# GoPiGoMod.net
KiCad netlist of a schematic drawn in EAGLE
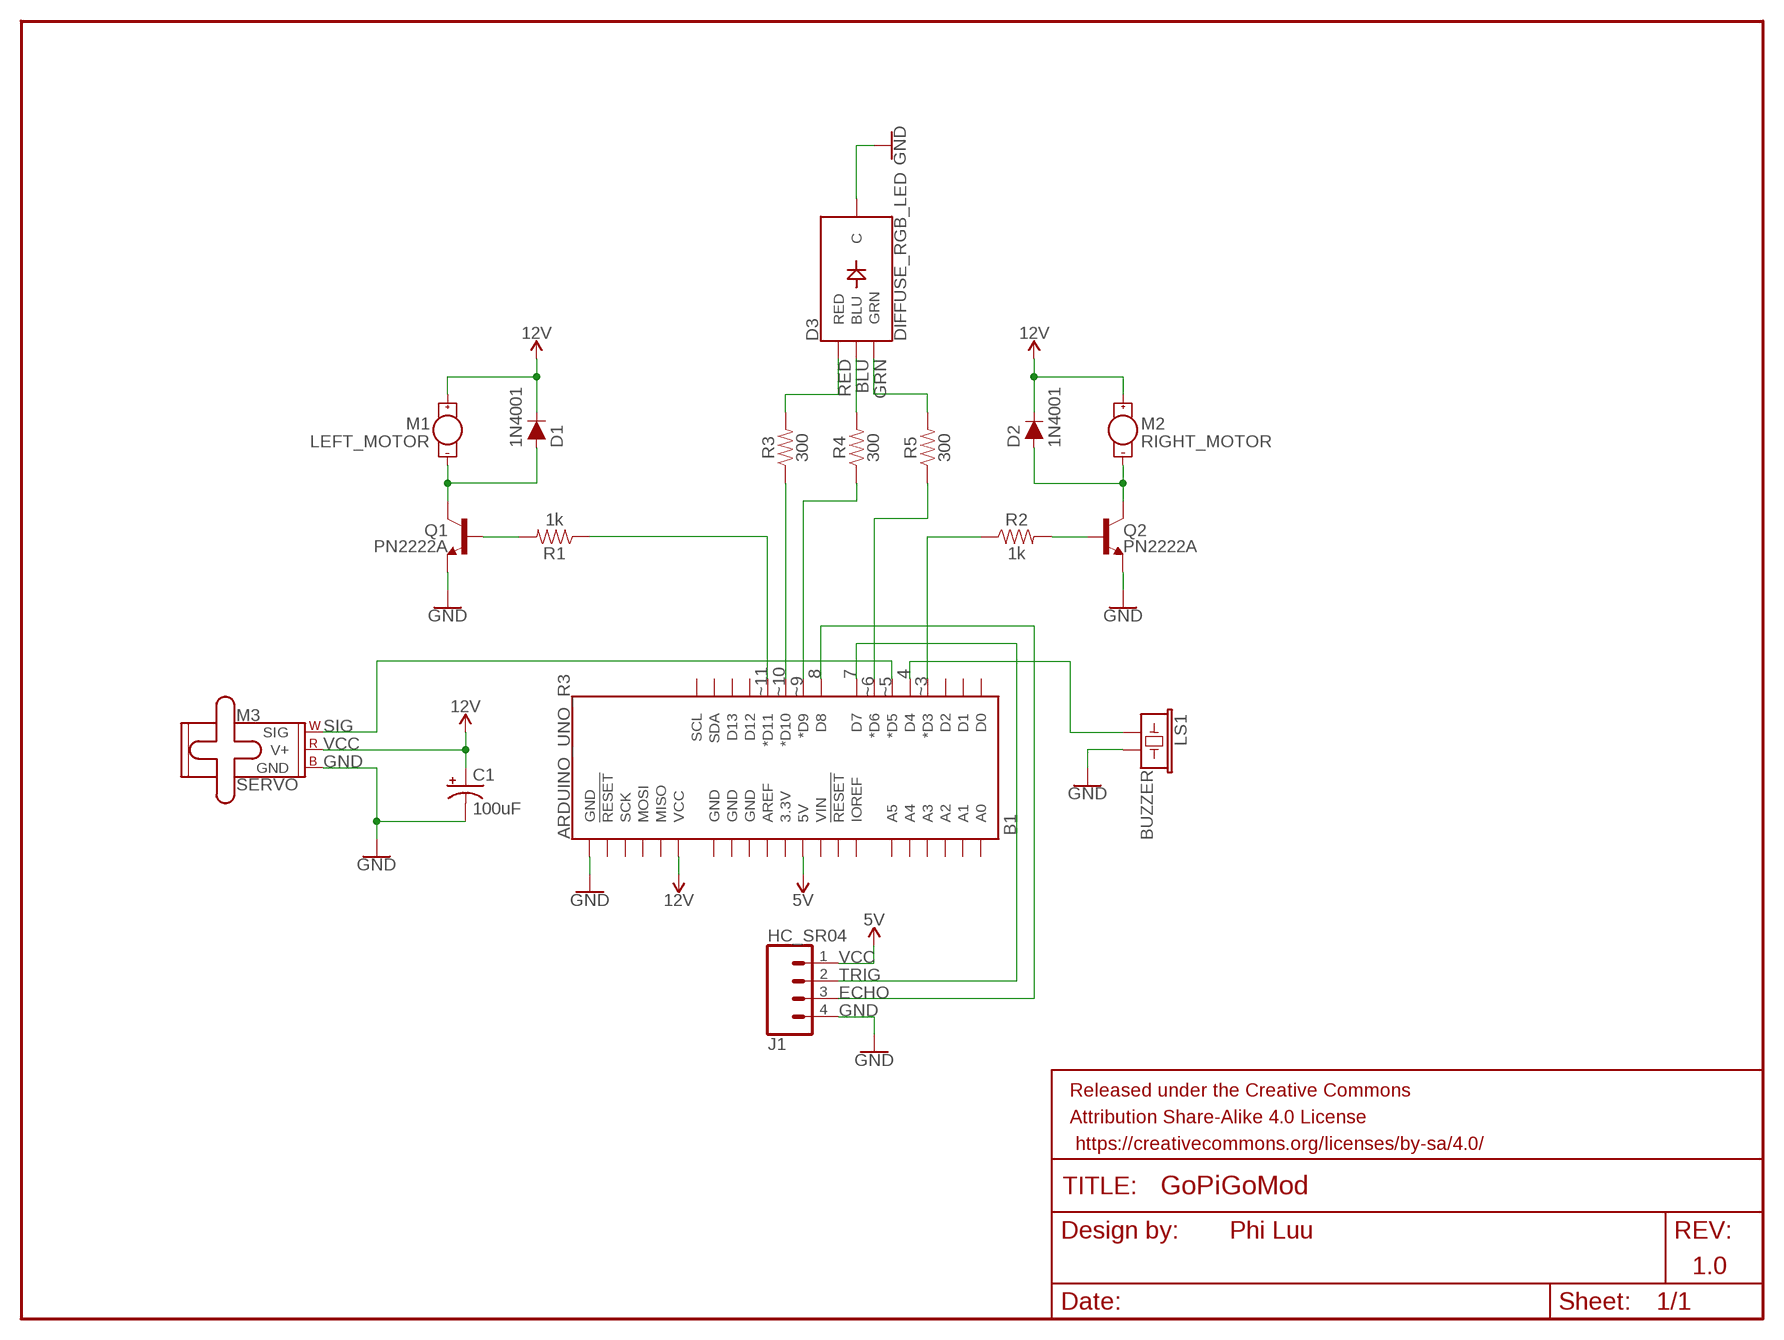
[diagram p0: schematic, sheet 1]

(export (version "E")
  (design (tool "Eeschema 10.0.6"))
  (components
    (comp (ref "B1")
      (value "ARDUINO_UNO_R3")
      (footprint "eagle-import:ARDUINO_R3")
      (libsource (lib "eagle-import") (part "ARDUINO_UNO_R3"))
    )
    (comp (ref "C1")
      (value "100uF")
      (footprint "eagle-import:CPOL-RADIAL-2.5MM-6.5MM")
      (libsource (lib "eagle-import") (part "100UF-POLAR-RADIAL-2.5MM-25V-20%"))
    )
    (comp (ref "D1")
      (value "1N4001")
      (footprint "eagle-import:DIODE-1N4001")
      (libsource (lib "eagle-import") (part "DIODE-PTH"))
    )
    (comp (ref "D2")
      (value "1N4001")
      (footprint "eagle-import:DIODE-1N4001")
      (libsource (lib "eagle-import") (part "DIODE-PTH"))
    )
    (comp (ref "D3")
      (value "DIFFUSE_RGB_LED")
      (footprint "eagle-import:LED-RGB-THRU")
      (libsource (lib "eagle-import") (part "LED-RGB-CCDIFFUSE"))
    )
    (comp (ref "FRAME1")
      (value "FRAME-LETTER")
      (footprint "eagle-import:CREATIVE_COMMONS")
      (libsource (lib "eagle-import") (part "FRAME-LETTER"))
    )
    (comp (ref "J1")
      (value "HC_SR04")
      (footprint "eagle-import:1X04")
      (libsource (lib "eagle-import") (part "CONN_04"))
    )
    (comp (ref "LS1")
      (value "BUZZER")
      (footprint "eagle-import:BUZZER-12MM")
      (libsource (lib "eagle-import") (part "BUZZER-PTH"))
    )
    (comp (ref "M1")
      (value "LEFT_MOTOR")
      (footprint "eagle-import:VIBE-MOTOR-10MM")
      (libsource (lib "eagle-import") (part "MOTOR10MM"))
    )
    (comp (ref "M2")
      (value "RIGHT_MOTOR")
      (footprint "eagle-import:VIBE-MOTOR-10MM")
      (libsource (lib "eagle-import") (part "MOTOR10MM"))
    )
    (comp (ref "M3")
      (value "SERVO")
      (footprint "eagle-import:1X03")
      (libsource (lib "eagle-import") (part "SERVO"))
    )
    (comp (ref "Q1")
      (value "PN2222A")
      (footprint "eagle-import:TO-92")
      (libsource (lib "eagle-import") (part "TRANS_NPN-P2N2222A"))
    )
    (comp (ref "Q2")
      (value "PN2222A")
      (footprint "eagle-import:TO-92")
      (libsource (lib "eagle-import") (part "TRANS_NPN-P2N2222A"))
    )
    (comp (ref "R1")
      (value "1k")
      (footprint "eagle-import:AXIAL-0.3")
      (libsource (lib "eagle-import") (part "1KOHM-HORIZ-1/4W-5%"))
    )
    (comp (ref "R2")
      (value "1k")
      (footprint "eagle-import:AXIAL-0.3")
      (libsource (lib "eagle-import") (part "1KOHM-HORIZ-1/4W-5%"))
    )
    (comp (ref "R3")
      (value "300")
      (footprint "eagle-import:AXIAL-0.3")
      (libsource (lib "eagle-import") (part "1KOHM-HORIZ-1/4W-5%"))
    )
    (comp (ref "R4")
      (value "300")
      (footprint "eagle-import:AXIAL-0.3")
      (libsource (lib "eagle-import") (part "1KOHM-HORIZ-1/4W-5%"))
    )
    (comp (ref "R5")
      (value "300")
      (footprint "eagle-import:AXIAL-0.3")
      (libsource (lib "eagle-import") (part "1KOHM-HORIZ-1/4W-5%"))
    )
  )
  (nets
    (net (code "1") (name "/4") (class "Default")
      (node (ref "B1") (pin "D4") (pinfunction "D4_D4") (pintype "bidirectional"))
      (node (ref "LS1") (pin "+") (pinfunction "1_+") (pintype "passive"))
    )
    (net (code "2") (name "/7") (class "Default")
      (node (ref "B1") (pin "D7") (pinfunction "D7_D7") (pintype "bidirectional"))
      (node (ref "J1") (pin "2") (pinfunction "2_2") (pintype "passive"))
    )
    (net (code "3") (name "/8") (class "Default")
      (node (ref "B1") (pin "D8") (pinfunction "D8_D8") (pintype "bidirectional"))
      (node (ref "J1") (pin "3") (pinfunction "3_3") (pintype "passive"))
    )
    (net (code "4") (name "/BLU") (class "Default")
      (node (ref "D3") (pin "4") (pinfunction "BLU_4") (pintype "bidirectional"))
      (node (ref "R4") (pin "P$2") (pinfunction "2_P$2") (pintype "passive"))
    )
    (net (code "5") (name "/GRN") (class "Default")
      (node (ref "D3") (pin "3") (pinfunction "GRN_3") (pintype "bidirectional"))
      (node (ref "R5") (pin "P$2") (pinfunction "2_P$2") (pintype "passive"))
    )
    (net (code "6") (name "/RED") (class "Default")
      (node (ref "D3") (pin "1") (pinfunction "RED_1") (pintype "bidirectional"))
      (node (ref "R3") (pin "P$2") (pinfunction "2_P$2") (pintype "passive"))
    )
    (net (code "7") (name "/~{3}") (class "Default")
      (node (ref "B1") (pin "D3") (pinfunction "*D3_D3") (pintype "bidirectional"))
      (node (ref "R2") (pin "P$1") (pinfunction "1_P$1") (pintype "passive"))
    )
    (net (code "8") (name "/~{5}") (class "Default")
      (node (ref "B1") (pin "D5") (pinfunction "*D5_D5") (pintype "bidirectional"))
      (node (ref "M3") (pin "1") (pinfunction "SIG_1") (pintype "bidirectional"))
    )
    (net (code "9") (name "/~{6}") (class "Default")
      (node (ref "B1") (pin "D6") (pinfunction "*D6_D6") (pintype "bidirectional"))
      (node (ref "R5") (pin "P$1") (pinfunction "1_P$1") (pintype "passive"))
    )
    (net (code "10") (name "/~{9}") (class "Default")
      (node (ref "B1") (pin "D9") (pinfunction "*D9_D9") (pintype "bidirectional"))
      (node (ref "R4") (pin "P$1") (pinfunction "1_P$1") (pintype "passive"))
    )
    (net (code "11") (name "/~{10}") (class "Default")
      (node (ref "B1") (pin "D10") (pinfunction "*D10_D10") (pintype "bidirectional"))
      (node (ref "R3") (pin "P$1") (pinfunction "1_P$1") (pintype "passive"))
    )
    (net (code "12") (name "/~{11}") (class "Default")
      (node (ref "B1") (pin "D11") (pinfunction "*D11_D11") (pintype "bidirectional"))
      (node (ref "R1") (pin "P$1") (pinfunction "1_P$1") (pintype "passive"))
    )
    (net (code "13") (name "5V") (class "Default")
      (node (ref "B1") (pin "5V") (pinfunction "5V_5V") (pintype "bidirectional"))
      (node (ref "J1") (pin "1") (pinfunction "1_1") (pintype "passive"))
    )
    (net (code "14") (name "12V") (class "Default")
      (node (ref "B1") (pin "VCC") (pinfunction "VCC_VCC") (pintype "bidirectional"))
      (node (ref "C1") (pin "1") (pinfunction "+_1") (pintype "passive"))
      (node (ref "D1") (pin "C") (pinfunction "C_C") (pintype "passive"))
      (node (ref "D2") (pin "C") (pinfunction "C_C") (pintype "passive"))
      (node (ref "M1") (pin "+") (pinfunction "+_+") (pintype "bidirectional"))
      (node (ref "M2") (pin "+") (pinfunction "+_+") (pintype "bidirectional"))
      (node (ref "M3") (pin "2") (pinfunction "V+_2") (pintype "bidirectional"))
    )
    (net (code "15") (name "GND") (class "Default")
      (node (ref "B1") (pin "GND@1") (pinfunction "GND_GND@1") (pintype "bidirectional"))
      (node (ref "C1") (pin "2") (pinfunction "-_2") (pintype "passive"))
      (node (ref "D3") (pin "2") (pinfunction "C_2") (pintype "bidirectional"))
      (node (ref "J1") (pin "4") (pinfunction "4_4") (pintype "passive"))
      (node (ref "LS1") (pin "-") (pinfunction "2_-") (pintype "passive"))
      (node (ref "M3") (pin "3") (pinfunction "GND_3") (pintype "bidirectional"))
      (node (ref "Q1") (pin "3") (pinfunction "E_3") (pintype "passive"))
      (node (ref "Q2") (pin "3") (pinfunction "E_3") (pintype "passive"))
    )
    (net (code "16") (name "Net-(Q1-B)") (class "Default")
      (node (ref "Q1") (pin "2") (pinfunction "B_2") (pintype "passive"))
      (node (ref "R1") (pin "P$2") (pinfunction "2_P$2") (pintype "passive"))
    )
    (net (code "17") (name "Net-(Q1-C)") (class "Default")
      (node (ref "D1") (pin "A") (pinfunction "A_A") (pintype "passive"))
      (node (ref "M1") (pin "-") (pinfunction "-_-") (pintype "bidirectional"))
      (node (ref "Q1") (pin "1") (pinfunction "C_1") (pintype "passive"))
    )
    (net (code "18") (name "Net-(Q2-B)") (class "Default")
      (node (ref "Q2") (pin "2") (pinfunction "B_2") (pintype "passive"))
      (node (ref "R2") (pin "P$2") (pinfunction "2_P$2") (pintype "passive"))
    )
    (net (code "19") (name "Net-(Q2-C)") (class "Default")
      (node (ref "D2") (pin "A") (pinfunction "A_A") (pintype "passive"))
      (node (ref "M2") (pin "-") (pinfunction "-_-") (pintype "bidirectional"))
      (node (ref "Q2") (pin "1") (pinfunction "C_1") (pintype "passive"))
    )
    (net (code "20") (name "unconnected-(B1-GND-PadGND@2)") (class "Default")
      (node (ref "B1") (pin "GND@2") (pinfunction "GND_GND@2") (pintype "bidirectional"))
    )
    (net (code "21") (name "unconnected-(B1-GND-PadGND@3)") (class "Default")
      (node (ref "B1") (pin "GND@3") (pinfunction "GND_GND@3") (pintype "bidirectional"))
    )
    (net (code "22") (name "unconnected-(B1-GND-PadGND@4)") (class "Default")
      (node (ref "B1") (pin "GND@4") (pinfunction "GND_GND@4") (pintype "bidirectional"))
    )
    (net (code "23") (name "unconnected-(B1-Pad3.3V)") (class "Default")
      (node (ref "B1") (pin "3.3V") (pinfunction "3.3V_3.3V") (pintype "bidirectional"))
    )
    (net (code "24") (name "unconnected-(B1-PadA0)") (class "Default")
      (node (ref "B1") (pin "A0") (pinfunction "A0_A0") (pintype "bidirectional"))
    )
    (net (code "25") (name "unconnected-(B1-PadA1)") (class "Default")
      (node (ref "B1") (pin "A1") (pinfunction "A1_A1") (pintype "bidirectional"))
    )
    (net (code "26") (name "unconnected-(B1-PadA2)") (class "Default")
      (node (ref "B1") (pin "A2") (pinfunction "A2_A2") (pintype "bidirectional"))
    )
    (net (code "27") (name "unconnected-(B1-PadA3)") (class "Default")
      (node (ref "B1") (pin "A3") (pinfunction "A3_A3") (pintype "bidirectional"))
    )
    (net (code "28") (name "unconnected-(B1-PadA4)") (class "Default")
      (node (ref "B1") (pin "A4") (pinfunction "A4_A4") (pintype "bidirectional"))
    )
    (net (code "29") (name "unconnected-(B1-PadA5)") (class "Default")
      (node (ref "B1") (pin "A5") (pinfunction "A5_A5") (pintype "bidirectional"))
    )
    (net (code "30") (name "unconnected-(B1-PadAREF)") (class "Default")
      (node (ref "B1") (pin "AREF") (pinfunction "AREF_AREF") (pintype "bidirectional"))
    )
    (net (code "31") (name "unconnected-(B1-PadD0)") (class "Default")
      (node (ref "B1") (pin "D0") (pinfunction "D0_D0") (pintype "bidirectional"))
    )
    (net (code "32") (name "unconnected-(B1-PadD1)") (class "Default")
      (node (ref "B1") (pin "D1") (pinfunction "D1_D1") (pintype "bidirectional"))
    )
    (net (code "33") (name "unconnected-(B1-PadD2)") (class "Default")
      (node (ref "B1") (pin "D2") (pinfunction "D2_D2") (pintype "bidirectional"))
    )
    (net (code "34") (name "unconnected-(B1-PadD12)") (class "Default")
      (node (ref "B1") (pin "D12") (pinfunction "D12_D12") (pintype "bidirectional"))
    )
    (net (code "35") (name "unconnected-(B1-PadD13)") (class "Default")
      (node (ref "B1") (pin "D13") (pinfunction "D13_D13") (pintype "bidirectional"))
    )
    (net (code "36") (name "unconnected-(B1-PadIOREF)") (class "Default")
      (node (ref "B1") (pin "IOREF") (pinfunction "IOREF_IOREF") (pintype "bidirectional"))
    )
    (net (code "37") (name "unconnected-(B1-PadMISO)") (class "Default")
      (node (ref "B1") (pin "MISO") (pinfunction "MISO_MISO") (pintype "bidirectional"))
    )
    (net (code "38") (name "unconnected-(B1-PadMOSI)") (class "Default")
      (node (ref "B1") (pin "MOSI") (pinfunction "MOSI_MOSI") (pintype "bidirectional"))
    )
    (net (code "39") (name "unconnected-(B1-PadSCK)") (class "Default")
      (node (ref "B1") (pin "SCK") (pinfunction "SCK_SCK") (pintype "bidirectional"))
    )
    (net (code "40") (name "unconnected-(B1-PadSCL)") (class "Default")
      (node (ref "B1") (pin "SCL") (pinfunction "SCL_SCL") (pintype "bidirectional"))
    )
    (net (code "41") (name "unconnected-(B1-PadSDA)") (class "Default")
      (node (ref "B1") (pin "SDA") (pinfunction "SDA_SDA") (pintype "bidirectional"))
    )
    (net (code "42") (name "unconnected-(B1-PadVIN)") (class "Default")
      (node (ref "B1") (pin "VIN") (pinfunction "VIN_VIN") (pintype "bidirectional"))
    )
    (net (code "43") (name "unconnected-(B1-~{RESET}-PadRESET@1)") (class "Default")
      (node (ref "B1") (pin "RESET@1") (pinfunction "~{RESET}_RESET@1") (pintype "bidirectional"))
    )
    (net (code "44") (name "unconnected-(B1-~{RESET}-PadRESET@2)") (class "Default")
      (node (ref "B1") (pin "RESET@2") (pinfunction "~{RESET}_RESET@2") (pintype "bidirectional"))
    )
  )
)
